# BATT_CONNECTOR.net
KiCad netlist of a schematic drawn in EAGLE
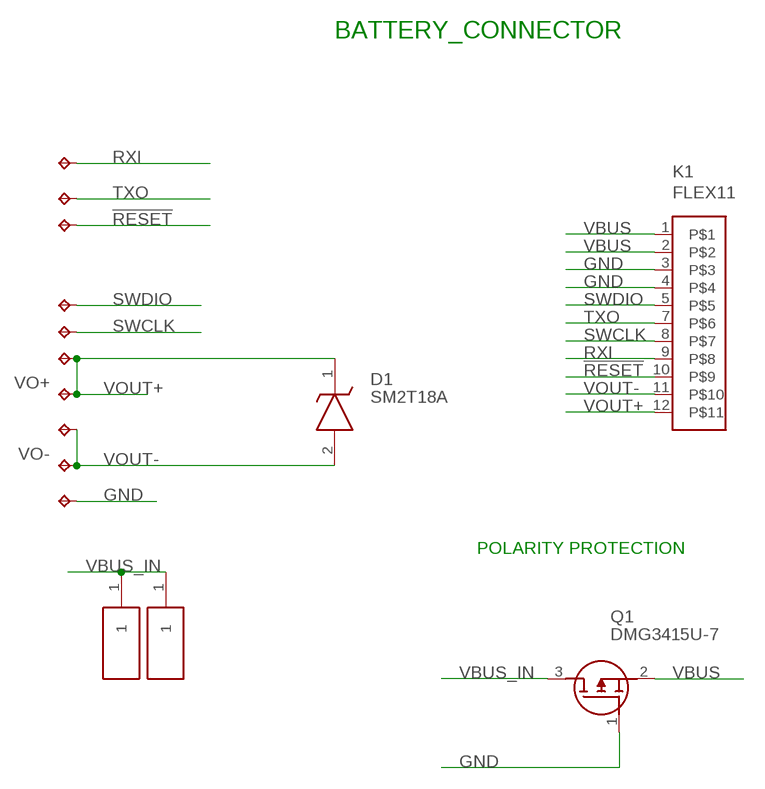
[diagram p0: schematic, sheet 1]

(export (version "E")
  (design (tool "Eeschema 10.0.6"))
  (components
    (comp (ref "!RESET")
      (value "TPB2,54")
      (footprint "eagle-import:B2,54")
      (libsource (lib "eagle-import") (part "TPB2,54"))
    )
    (comp (ref "D1")
      (value "SM2T18A")
      (footprint "eagle-import:SM2T18A")
      (fields (field (name "MOUSER_PART_NUMBER") "511-SM2T18A"))
      (libsource (lib "eagle-import") (part "SM2T18A"))
    )
    (comp (ref "GND")
      (value "TPB2,54")
      (footprint "eagle-import:B2,54")
      (libsource (lib "eagle-import") (part "TPB2,54"))
    )
    (comp (ref "H1")
      (value "S1761-42R")
      (footprint "eagle-import:S176142R")
      (fields (field (name "MOUSER_PART_NUMBER") "855-S1761-42R"))
      (libsource (lib "eagle-import") (part "S1761-42R"))
    )
    (comp (ref "H2")
      (value "S1761-42R")
      (footprint "eagle-import:S176142R")
      (fields (field (name "MOUSER_PART_NUMBER") "855-S1761-42R"))
      (libsource (lib "eagle-import") (part "S1761-42R"))
    )
    (comp (ref "K1")
      (value "FLEX11")
      (footprint "eagle-import:FLEX11")
      (libsource (lib "eagle-import") (part "FLEX11"))
    )
    (comp (ref "Q1")
      (value "DMG3415U-7")
      (footprint "eagle-import:SSM3J332RLFT")
      (fields
        (field (name "ARROW_PART_NUMBER") "SSM3J338R,LF")
        (field (name "MOUSER_PART_NUMBER") "757-SSM3J338RLF")
      )
      (libsource (lib "eagle-import") (part "SSM3J338R,LF"))
    )
    (comp (ref "RXI")
      (value "TPB2,54")
      (footprint "eagle-import:B2,54")
      (libsource (lib "eagle-import") (part "TPB2,54"))
    )
    (comp (ref "SWCLK")
      (value "TPB2,54")
      (footprint "eagle-import:B2,54")
      (libsource (lib "eagle-import") (part "TPB2,54"))
    )
    (comp (ref "SWDIO")
      (value "TPB2,54")
      (footprint "eagle-import:B2,54")
      (libsource (lib "eagle-import") (part "TPB2,54"))
    )
    (comp (ref "TXO")
      (value "TPB2,54")
      (footprint "eagle-import:B2,54")
      (libsource (lib "eagle-import") (part "TPB2,54"))
    )
    (comp (ref "VO+")
      (value "TPB2,54")
      (footprint "eagle-import:B2,54")
      (libsource (lib "eagle-import") (part "TPB2,54"))
    )
    (comp (ref "VO-")
      (value "TPB2,54")
      (footprint "eagle-import:B2,54")
      (libsource (lib "eagle-import") (part "TPB2,54"))
    )
    (comp (ref "VOUT+1")
      (value "TPB2,54")
      (footprint "eagle-import:B2,54")
      (libsource (lib "eagle-import") (part "TPB2,54"))
    )
    (comp (ref "VOUT-1")
      (value "TPB2,54")
      (footprint "eagle-import:B2,54")
      (libsource (lib "eagle-import") (part "TPB2,54"))
    )
  )
  (nets
    (net (code "1") (name "/GND") (class "Default")
      (node (ref "GND") (pin "TP") (pinfunction "TP_TP") (pintype "input"))
      (node (ref "K1") (pin "3") (pinfunction "P$3_3") (pintype "bidirectional"))
      (node (ref "K1") (pin "4") (pinfunction "P$4_4") (pintype "bidirectional"))
      (node (ref "Q1") (pin "1") (pinfunction "G_1") (pintype "bidirectional"))
    )
    (net (code "2") (name "/RXI") (class "Default")
      (node (ref "K1") (pin "9") (pinfunction "P$8_9") (pintype "bidirectional"))
      (node (ref "RXI") (pin "TP") (pinfunction "TP_TP") (pintype "input"))
    )
    (net (code "3") (name "/SWCLK") (class "Default")
      (node (ref "K1") (pin "8") (pinfunction "P$7_8") (pintype "bidirectional"))
      (node (ref "SWCLK") (pin "TP") (pinfunction "TP_TP") (pintype "input"))
    )
    (net (code "4") (name "/SWDIO") (class "Default")
      (node (ref "K1") (pin "5") (pinfunction "P$5_5") (pintype "bidirectional"))
      (node (ref "SWDIO") (pin "TP") (pinfunction "TP_TP") (pintype "input"))
    )
    (net (code "5") (name "/TXO") (class "Default")
      (node (ref "K1") (pin "7") (pinfunction "P$6_7") (pintype "bidirectional"))
      (node (ref "TXO") (pin "TP") (pinfunction "TP_TP") (pintype "input"))
    )
    (net (code "6") (name "/VBUS") (class "Default")
      (node (ref "K1") (pin "1") (pinfunction "P$1_1") (pintype "bidirectional"))
      (node (ref "K1") (pin "2") (pinfunction "P$2_2") (pintype "bidirectional"))
      (node (ref "Q1") (pin "2") (pinfunction "S_2") (pintype "bidirectional"))
    )
    (net (code "7") (name "/VBUS_IN") (class "Default")
      (node (ref "H1") (pin "1") (pinfunction "1_1") (pintype "bidirectional"))
      (node (ref "H2") (pin "1") (pinfunction "1_1") (pintype "bidirectional"))
      (node (ref "Q1") (pin "3") (pinfunction "D_3") (pintype "bidirectional"))
    )
    (net (code "8") (name "/VOUT+") (class "Default")
      (node (ref "D1") (pin "1") (pinfunction "K_1") (pintype "bidirectional"))
      (node (ref "K1") (pin "12") (pinfunction "P$11_12") (pintype "bidirectional"))
      (node (ref "VO+") (pin "TP") (pinfunction "TP_TP") (pintype "input"))
      (node (ref "VOUT+1") (pin "TP") (pinfunction "TP_TP") (pintype "input"))
    )
    (net (code "9") (name "/VOUT-") (class "Default")
      (node (ref "D1") (pin "2") (pinfunction "A_2") (pintype "bidirectional"))
      (node (ref "K1") (pin "11") (pinfunction "P$10_11") (pintype "bidirectional"))
      (node (ref "VO-") (pin "TP") (pinfunction "TP_TP") (pintype "input"))
      (node (ref "VOUT-1") (pin "TP") (pinfunction "TP_TP") (pintype "input"))
    )
    (net (code "10") (name "/~{RESET}") (class "Default")
      (node (ref "!RESET") (pin "TP") (pinfunction "TP_TP") (pintype "input"))
      (node (ref "K1") (pin "10") (pinfunction "P$9_10") (pintype "bidirectional"))
    )
  )
)
